# Sheet1.net
KiCad netlist of a schematic drawn in Altium Designer
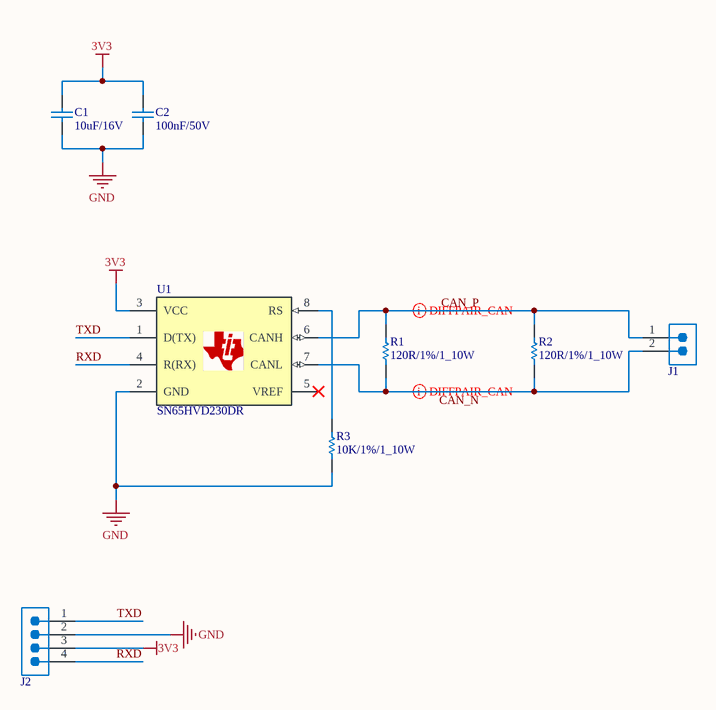
[diagram p0: Sheet1.SchDoc]

(export (version "E")
  (design (tool "Eeschema 10.0.6"))
  (components
    (comp (ref "C1")
      (value "10uF/16V")
      (footprint "CAP_0603")
      (description "CAP, size 0603, 10uF, 16V")
      (fields (field (name "SUPPLY PART NUMBER") "Tụ Gốm 0603 10uF 16V"))
      (libsource (lib "BluetoothTracking") (part "Ceramic_Cap_10uF_16V_0603"))
    )
    (comp (ref "C2")
      (value "100nF/50V")
      (footprint "CAP_0603")
      (description "CAP, size 0603, 100nF, 50V")
      (fields (field (name "SUPPLY PART NUMBER") "Tụ Gốm 0603 100nF (0.1uF) 50V"))
      (libsource (lib "BluetoothTracking") (part "Ceramic_Cap_100nF_50V_0603"))
    )
    (comp (ref "J1")
      (value "2.54mm_2P")
      (footprint "Header_2.54mm_2P")
      (description "Hàng Rào Đực Đơn 2.54mm 40 Chân 1 Hàng Cao 11.2mm Xuyên Lỗ")
      (libsource (lib "BluetoothTracking") (part "Header_2.54mm_2P"))
    )
    (comp (ref "J2")
      (value "2.54mm_4P")
      (footprint "Header_2.54mm_4P")
      (description "Hàng Rào Đực Đơn 2.54mm 40 Chân 1 Hàng Cao 11.2mm Xuyên Lỗ")
      (libsource (lib "BluetoothTracking") (part "Header_2.54mm_4P"))
    )
    (comp (ref "R1")
      (value "120R/1%/1_10W")
      (footprint "Resistor_0603")
      (description "Resistor 0603 120 Ohm 1% 1_10W")
      (fields (field (name "SUPPLY PART NUMBER") "Điện Trở 120 Ohm 0603 1%"))
      (libsource (lib "BluetoothTracking") (part "Res_120R_0603_1%"))
    )
    (comp (ref "R2")
      (value "120R/1%/1_10W")
      (footprint "Resistor_0603")
      (description "Resistor 0603 120 Ohm 1% 1_10W")
      (fields (field (name "SUPPLY PART NUMBER") "Điện Trở 120 Ohm 0603 1%"))
      (libsource (lib "BluetoothTracking") (part "Res_120R_0603_1%"))
    )
    (comp (ref "R3")
      (value "10K/1%/1_10W")
      (footprint "Resistor_0603")
      (description "Resistor 0603 10KOhm 1% 1_10W")
      (fields (field (name "SUPPLY PART NUMBER") "Điện Trở 10 KOhm 0603 1%"))
      (libsource (lib "BluetoothTracking") (part "Res_10K_0603_1%"))
    )
    (comp (ref "U1")
      (value "SN65HVD230DR")
      (footprint "SOIC-8")
      (description "1/1 Transceiver Half CANbus")
      (fields (field (name "SUPPLY PART NUMBER") "SN65HVD230DR CAN Transceiver 8-SOIC"))
      (libsource (lib "BluetoothTracking") (part "SN65HVD230DR"))
    )
  )
  (nets
    (net (code "1") (name "/CAN_N") (class "Default")
      (node (ref "J1") (pin "2") (pinfunction "2_2") (pintype "passive"))
      (node (ref "R1") (pin "1") (pinfunction "1_1") (pintype "passive"))
      (node (ref "R2") (pin "1") (pinfunction "1_1") (pintype "passive"))
      (node (ref "U1") (pin "7") (pinfunction "CANL_7") (pintype "bidirectional"))
    )
    (net (code "2") (name "/CAN_P") (class "Default")
      (node (ref "J1") (pin "1") (pinfunction "1_1") (pintype "passive"))
      (node (ref "R1") (pin "2") (pinfunction "2_2") (pintype "passive"))
      (node (ref "R2") (pin "2") (pinfunction "2_2") (pintype "passive"))
      (node (ref "U1") (pin "6") (pinfunction "CANH_6") (pintype "bidirectional"))
    )
    (net (code "3") (name "/RXD") (class "Default")
      (node (ref "J2") (pin "4") (pinfunction "4_4") (pintype "passive"))
      (node (ref "U1") (pin "4") (pinfunction "R(RX)_4") (pintype "passive"))
    )
    (net (code "4") (name "/TXD") (class "Default")
      (node (ref "J2") (pin "1") (pinfunction "1_1") (pintype "passive"))
      (node (ref "U1") (pin "1") (pinfunction "D(TX)_1") (pintype "passive"))
    )
    (net (code "5") (name "3V3") (class "Default")
      (node (ref "C1") (pin "2") (pinfunction "2_2") (pintype "passive"))
      (node (ref "C2") (pin "2") (pinfunction "2_2") (pintype "passive"))
      (node (ref "J2") (pin "3") (pinfunction "3_3") (pintype "passive"))
      (node (ref "U1") (pin "3") (pinfunction "VCC_3") (pintype "power_in"))
    )
    (net (code "6") (name "GND") (class "Default")
      (node (ref "C1") (pin "1") (pinfunction "1_1") (pintype "passive"))
      (node (ref "C2") (pin "1") (pinfunction "1_1") (pintype "passive"))
      (node (ref "J2") (pin "2") (pinfunction "2_2") (pintype "passive"))
      (node (ref "R3") (pin "1") (pinfunction "1_1") (pintype "passive"))
      (node (ref "U1") (pin "2") (pinfunction "GND_2") (pintype "power_in"))
    )
    (net (code "7") (name "Net-(U1-RS)") (class "Default")
      (node (ref "R3") (pin "2") (pinfunction "2_2") (pintype "passive"))
      (node (ref "U1") (pin "8") (pinfunction "RS_8") (pintype "input"))
    )
    (net (code "8") (name "unconnected-(U1-VREF-Pad5)") (class "Default")
      (node (ref "U1") (pin "5") (pinfunction "VREF_5") (pintype "power_in+no_connect"))
    )
  )
)
